# CW308T_EMF32GG11.net
KiCad netlist of a schematic drawn in Altium Designer
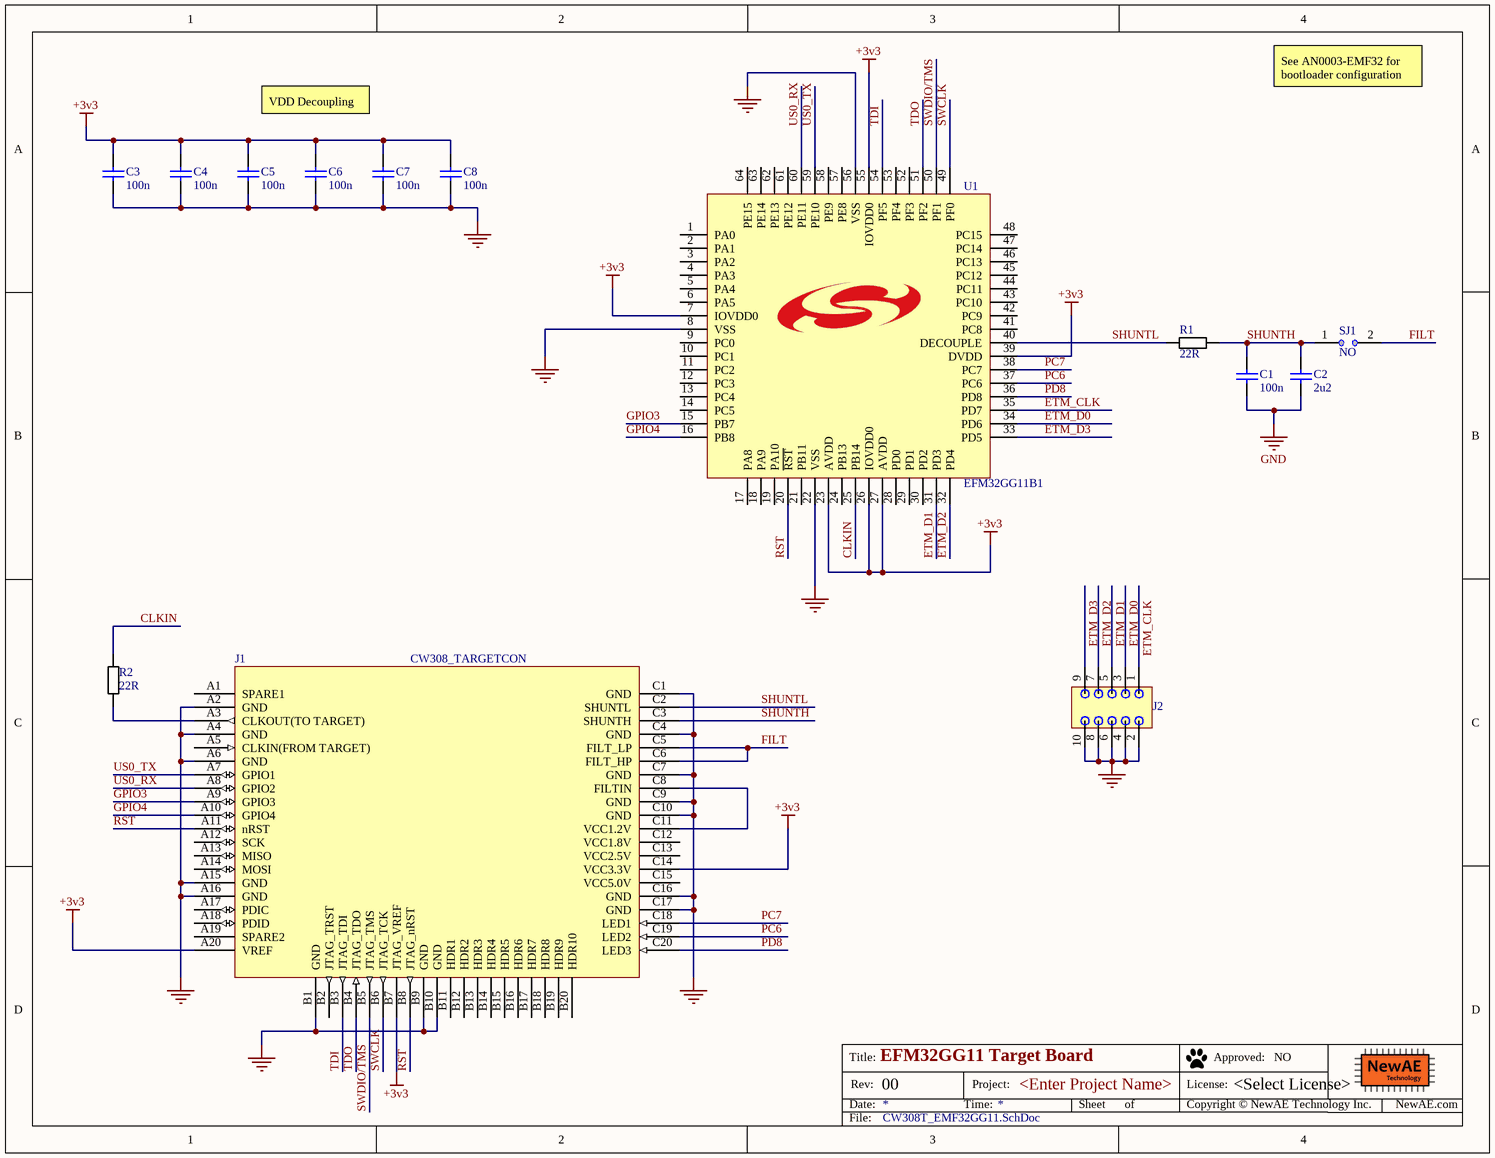
[diagram p0: CW308T_EMF32GG11.SchDoc]

(export (version "E")
  (design (tool "Eeschema 10.0.6"))
  (components
    (comp (ref "C1")
      (value "100n")
      (footprint "CAPC0603_M")
      (description "100n, 0603")
      (fields (field (name "PART NUMBER") "CCHIP-100n-0603"))
      (libsource (lib "NewAE_AltiumLib") (part "CAP"))
    )
    (comp (ref "C2")
      (value "2u2")
      (footprint "CAPC0603_M")
      (description "2u2, 0603")
      (fields (field (name "PART NUMBER") "CCHIP-2u2-0603"))
      (libsource (lib "NewAE_AltiumLib") (part "CAP"))
    )
    (comp (ref "C3")
      (value "100n")
      (footprint "CAPC0603_M")
      (description "100n, 0603")
      (fields (field (name "PART NUMBER") "CCHIP-100n-0603"))
      (libsource (lib "NewAE_AltiumLib") (part "CAP"))
    )
    (comp (ref "C4")
      (value "100n")
      (footprint "CAPC0603_M")
      (description "100n, 0603")
      (fields (field (name "PART NUMBER") "CCHIP-100n-0603"))
      (libsource (lib "NewAE_AltiumLib") (part "CAP"))
    )
    (comp (ref "C5")
      (value "100n")
      (footprint "CAPC0603_M")
      (description "100n, 0603")
      (fields (field (name "PART NUMBER") "CCHIP-100n-0603"))
      (libsource (lib "NewAE_AltiumLib") (part "CAP"))
    )
    (comp (ref "C6")
      (value "100n")
      (footprint "CAPC0603_M")
      (description "100n, 0603")
      (fields (field (name "PART NUMBER") "CCHIP-100n-0603"))
      (libsource (lib "NewAE_AltiumLib") (part "CAP"))
    )
    (comp (ref "C7")
      (value "100n")
      (footprint "CAPC0603_M")
      (description "100n, 0603")
      (fields (field (name "PART NUMBER") "CCHIP-100n-0603"))
      (libsource (lib "NewAE_AltiumLib") (part "CAP"))
    )
    (comp (ref "C8")
      (value "100n")
      (footprint "CAPC0603_M")
      (description "100n, 0603")
      (fields (field (name "PART NUMBER") "CCHIP-100n-0603"))
      (libsource (lib "NewAE_AltiumLib") (part "CAP"))
    )
    (comp (ref "J1")
      (value "CW308_TARGETCON")
      (footprint "CW308_TBOARD_CONN")
      (description "CW308 \"Standard\" Target Board Connector")
      (fields (field (name "PART NUMBER") "CW308_TBOARD"))
      (libsource (lib "NewAE_AltiumLib") (part "CW308_TBOARD"))
    )
    (comp (ref "J2")
      (value "1296-T10")
      (footprint "1296-T10")
      (description "Header, 10-pin, SMD, 0.05\"")
      (libsource (lib "NewAE_AltiumLib") (part "CON10_2ROW"))
    )
    (comp (ref "R1")
      (value "22R")
      (footprint "RESC1608X55N")
      (description "22R res, 0603, 1%, 1/10W")
      (fields (field (name "PART NUMBER") "RCHIP-22R-0603") (field (name "TOLERANCE") "1%"))
      (libsource (lib "NewAE_AltiumLib") (part "RES-EU"))
    )
    (comp (ref "R2")
      (value "22R")
      (footprint "RESC1608X55N")
      (description "22R res, 0603, 1%, 1/10W")
      (fields (field (name "PART NUMBER") "RCHIP-22R-0603") (field (name "TOLERANCE") "1%"))
      (libsource (lib "") (part "RES-EU_1"))
    )
    (comp (ref "SJ1")
      (value "NO")
      (footprint "SJ_2S_NO")
      (description "Solder Jumper, NO")
      (fields (field (name "PART NUMBER") "SJ_2S_NO"))
      (libsource (lib "NewAE_AltiumLib") (part "SJ_2S_NO"))
    )
    (comp (ref "U1")
      (value "EFM32GG11B1")
      (footprint "TQFP50P1200X1200X120-64N")
      (description "MCU Giant Gecko 11 Ultra Low Power MCU, Cortex-M4 72MHz QFP64 2048kB(Flash) 512kB(RAM) 53GPIO")
      (libsource (lib "NewAE_AltiumLib") (part "EFM32GG11B1"))
    )
  )
  (nets
    (net (code "1") (name "+3v3") (class "Default")
      (node (ref "C3") (pin "1") (pinfunction "1_1") (pintype "passive"))
      (node (ref "C4") (pin "1") (pinfunction "1_1") (pintype "passive"))
      (node (ref "C5") (pin "1") (pinfunction "1_1") (pintype "passive"))
      (node (ref "C6") (pin "1") (pinfunction "1_1") (pintype "passive"))
      (node (ref "C7") (pin "1") (pinfunction "1_1") (pintype "passive"))
      (node (ref "C8") (pin "1") (pinfunction "1_1") (pintype "passive"))
      (node (ref "J1") (pin "A20") (pinfunction "VREF_A20") (pintype "tri_state"))
      (node (ref "J1") (pin "B7") (pinfunction "JTAG_VREF_B7") (pintype "tri_state"))
      (node (ref "J1") (pin "C14") (pinfunction "VCC3.3V_C14") (pintype "power_in"))
      (node (ref "U1") (pin "23") (pinfunction "AVDD_23") (pintype "passive"))
      (node (ref "U1") (pin "26") (pinfunction "IOVDD0_26") (pintype "passive"))
      (node (ref "U1") (pin "27") (pinfunction "AVDD_27") (pintype "passive"))
      (node (ref "U1") (pin "39") (pinfunction "DVDD_39") (pintype "passive"))
      (node (ref "U1") (pin "55") (pinfunction "IOVDD0_55") (pintype "passive"))
      (node (ref "U1") (pin "7") (pinfunction "IOVDD0_7") (pintype "passive"))
    )
    (net (code "2") (name "/CLKIN") (class "Default")
      (node (ref "R2") (pin "1") (pinfunction "1_1") (pintype "passive"))
      (node (ref "U1") (pin "25") (pinfunction "PB14_25") (pintype "passive"))
    )
    (net (code "3") (name "/ETM_CLK") (class "Default")
      (node (ref "J2") (pin "1") (pinfunction "1_1") (pintype "passive"))
      (node (ref "U1") (pin "35") (pinfunction "PD7_35") (pintype "passive"))
    )
    (net (code "4") (name "/ETM_D0") (class "Default")
      (node (ref "J2") (pin "3") (pinfunction "3_3") (pintype "passive"))
      (node (ref "U1") (pin "34") (pinfunction "PD6_34") (pintype "passive"))
    )
    (net (code "5") (name "/ETM_D1") (class "Default")
      (node (ref "J2") (pin "5") (pinfunction "5_5") (pintype "passive"))
      (node (ref "U1") (pin "31") (pinfunction "PD3_31") (pintype "passive"))
    )
    (net (code "6") (name "/ETM_D2") (class "Default")
      (node (ref "J2") (pin "7") (pinfunction "7_7") (pintype "passive"))
      (node (ref "U1") (pin "32") (pinfunction "PD4_32") (pintype "passive"))
    )
    (net (code "7") (name "/ETM_D3") (class "Default")
      (node (ref "J2") (pin "9") (pinfunction "9_9") (pintype "passive"))
      (node (ref "U1") (pin "33") (pinfunction "PD5_33") (pintype "passive"))
    )
    (net (code "8") (name "/FILT") (class "Default")
      (node (ref "J1") (pin "C5") (pinfunction "FILT_LP_C5") (pintype "passive"))
      (node (ref "J1") (pin "C6") (pinfunction "FILT_HP_C6") (pintype "passive"))
      (node (ref "SJ1") (pin "2") (pinfunction "2_2") (pintype "passive"))
    )
    (net (code "9") (name "/GPIO3") (class "Default")
      (node (ref "J1") (pin "A9") (pinfunction "GPIO3_A9") (pintype "bidirectional"))
      (node (ref "U1") (pin "15") (pinfunction "PB7_15") (pintype "passive"))
    )
    (net (code "10") (name "/GPIO4") (class "Default")
      (node (ref "J1") (pin "A10") (pinfunction "GPIO4_A10") (pintype "bidirectional"))
      (node (ref "U1") (pin "16") (pinfunction "PB8_16") (pintype "passive"))
    )
    (net (code "11") (name "/PC6") (class "Default")
      (node (ref "J1") (pin "C19") (pinfunction "LED2_C19") (pintype "input"))
      (node (ref "U1") (pin "37") (pinfunction "PC6_37") (pintype "passive"))
    )
    (net (code "12") (name "/PC7") (class "Default")
      (node (ref "J1") (pin "C18") (pinfunction "LED1_C18") (pintype "input"))
      (node (ref "U1") (pin "38") (pinfunction "PC7_38") (pintype "passive"))
    )
    (net (code "13") (name "/PD8") (class "Default")
      (node (ref "J1") (pin "C20") (pinfunction "LED3_C20") (pintype "input"))
      (node (ref "U1") (pin "36") (pinfunction "PD8_36") (pintype "passive"))
    )
    (net (code "14") (name "/RST") (class "Default")
      (node (ref "J1") (pin "A11") (pinfunction "nRST_A11") (pintype "bidirectional"))
      (node (ref "J1") (pin "B8") (pinfunction "JTAG_nRST_B8") (pintype "output"))
      (node (ref "U1") (pin "20") (pinfunction "~{RST}_20") (pintype "passive"))
    )
    (net (code "15") (name "/SHUNTH") (class "Default")
      (node (ref "C1") (pin "1") (pinfunction "1_1") (pintype "passive"))
      (node (ref "C2") (pin "1") (pinfunction "1_1") (pintype "passive"))
      (node (ref "J1") (pin "C3") (pinfunction "SHUNTH_C3") (pintype "passive"))
      (node (ref "R1") (pin "2") (pinfunction "2_2") (pintype "passive"))
      (node (ref "SJ1") (pin "1") (pinfunction "1_1") (pintype "passive"))
    )
    (net (code "16") (name "/SHUNTL") (class "Default")
      (node (ref "J1") (pin "C2") (pinfunction "SHUNTL_C2") (pintype "passive"))
      (node (ref "R1") (pin "1") (pinfunction "1_1") (pintype "passive"))
      (node (ref "U1") (pin "40") (pinfunction "DECOUPLE_40") (pintype "passive"))
    )
    (net (code "17") (name "/SWCLK") (class "Default")
      (node (ref "J1") (pin "B6") (pinfunction "JTAG_TCK_B6") (pintype "output"))
      (node (ref "U1") (pin "49") (pinfunction "PF0_49") (pintype "passive"))
    )
    (net (code "18") (name "/SWDIO{slash}TMS") (class "Default")
      (node (ref "J1") (pin "B5") (pinfunction "JTAG_TMS_B5") (pintype "output"))
      (node (ref "U1") (pin "50") (pinfunction "PF1_50") (pintype "passive"))
    )
    (net (code "19") (name "/TDI") (class "Default")
      (node (ref "J1") (pin "B3") (pinfunction "JTAG_TDI_B3") (pintype "output"))
      (node (ref "U1") (pin "54") (pinfunction "PF5_54") (pintype "passive"))
    )
    (net (code "20") (name "/TDO") (class "Default")
      (node (ref "J1") (pin "B4") (pinfunction "JTAG_TDO_B4") (pintype "input"))
      (node (ref "U1") (pin "51") (pinfunction "PF2_51") (pintype "passive"))
    )
    (net (code "21") (name "/US0_RX") (class "Default")
      (node (ref "J1") (pin "A8") (pinfunction "GPIO2_A8") (pintype "bidirectional"))
      (node (ref "U1") (pin "60") (pinfunction "PE11_60") (pintype "passive"))
    )
    (net (code "22") (name "/US0_TX") (class "Default")
      (node (ref "J1") (pin "A7") (pinfunction "GPIO1_A7") (pintype "bidirectional"))
      (node (ref "U1") (pin "59") (pinfunction "PE10_59") (pintype "passive"))
    )
    (net (code "23") (name "GND") (class "Default")
      (node (ref "C1") (pin "2") (pinfunction "2_2") (pintype "passive"))
      (node (ref "C2") (pin "2") (pinfunction "2_2") (pintype "passive"))
      (node (ref "C3") (pin "2") (pinfunction "2_2") (pintype "passive"))
      (node (ref "C4") (pin "2") (pinfunction "2_2") (pintype "passive"))
      (node (ref "C5") (pin "2") (pinfunction "2_2") (pintype "passive"))
      (node (ref "C6") (pin "2") (pinfunction "2_2") (pintype "passive"))
      (node (ref "C7") (pin "2") (pinfunction "2_2") (pintype "passive"))
      (node (ref "C8") (pin "2") (pinfunction "2_2") (pintype "passive"))
      (node (ref "J1") (pin "A15") (pinfunction "GND_A15") (pintype "passive"))
      (node (ref "J1") (pin "A16") (pinfunction "GND_A16") (pintype "passive"))
      (node (ref "J1") (pin "A2") (pinfunction "GND_A2") (pintype "passive"))
      (node (ref "J1") (pin "A4") (pinfunction "GND_A4") (pintype "passive"))
      (node (ref "J1") (pin "A6") (pinfunction "GND_A6") (pintype "power_in"))
      (node (ref "J1") (pin "B1") (pinfunction "GND_B1") (pintype "passive"))
      (node (ref "J1") (pin "B10") (pinfunction "GND_B10") (pintype "passive"))
      (node (ref "J1") (pin "B9") (pinfunction "GND_B9") (pintype "passive"))
      (node (ref "J1") (pin "C1") (pinfunction "GND_C1") (pintype "power_in"))
      (node (ref "J1") (pin "C10") (pinfunction "GND_C10") (pintype "power_in"))
      (node (ref "J1") (pin "C16") (pinfunction "GND_C16") (pintype "power_in"))
      (node (ref "J1") (pin "C17") (pinfunction "GND_C17") (pintype "power_in"))
      (node (ref "J1") (pin "C4") (pinfunction "GND_C4") (pintype "power_in"))
      (node (ref "J1") (pin "C7") (pinfunction "GND_C7") (pintype "power_in"))
      (node (ref "J1") (pin "C9") (pinfunction "GND_C9") (pintype "power_in"))
      (node (ref "J2") (pin "10") (pinfunction "10_10") (pintype "passive"))
      (node (ref "J2") (pin "2") (pinfunction "2_2") (pintype "passive"))
      (node (ref "J2") (pin "4") (pinfunction "4_4") (pintype "passive"))
      (node (ref "J2") (pin "6") (pinfunction "6_6") (pintype "passive"))
      (node (ref "J2") (pin "8") (pinfunction "8_8") (pintype "passive"))
      (node (ref "U1") (pin "22") (pinfunction "VSS_22") (pintype "passive"))
      (node (ref "U1") (pin "56") (pinfunction "VSS_56") (pintype "passive"))
      (node (ref "U1") (pin "8") (pinfunction "VSS_8") (pintype "passive"))
    )
    (net (code "24") (name "Net-(J1-CLKOUT(TO_TARGET))") (class "Default")
      (node (ref "J1") (pin "A3") (pinfunction "CLKOUT(TO_TARGET)_A3") (pintype "output"))
      (node (ref "R2") (pin "2") (pinfunction "2_2") (pintype "passive"))
    )
    (net (code "25") (name "Net-(J1-FILTIN)") (class "Default")
      (node (ref "J1") (pin "C11") (pinfunction "VCC1.2V_C11") (pintype "power_in"))
      (node (ref "J1") (pin "C8") (pinfunction "FILTIN_C8") (pintype "passive"))
    )
    (net (code "26") (name "unconnected-(J1-CLKIN(FROM_TARGET)-PadA5)") (class "Default")
      (node (ref "J1") (pin "A5") (pinfunction "CLKIN(FROM_TARGET)_A5") (pintype "input"))
    )
    (net (code "27") (name "unconnected-(J1-HDR1-PadB11)") (class "Default")
      (node (ref "J1") (pin "B11") (pinfunction "HDR1_B11") (pintype "passive"))
    )
    (net (code "28") (name "unconnected-(J1-HDR2-PadB12)") (class "Default")
      (node (ref "J1") (pin "B12") (pinfunction "HDR2_B12") (pintype "passive"))
    )
    (net (code "29") (name "unconnected-(J1-HDR3-PadB13)") (class "Default")
      (node (ref "J1") (pin "B13") (pinfunction "HDR3_B13") (pintype "passive"))
    )
    (net (code "30") (name "unconnected-(J1-HDR4-PadB14)") (class "Default")
      (node (ref "J1") (pin "B14") (pinfunction "HDR4_B14") (pintype "passive"))
    )
    (net (code "31") (name "unconnected-(J1-HDR5-PadB15)") (class "Default")
      (node (ref "J1") (pin "B15") (pinfunction "HDR5_B15") (pintype "passive"))
    )
    (net (code "32") (name "unconnected-(J1-HDR6-PadB16)") (class "Default")
      (node (ref "J1") (pin "B16") (pinfunction "HDR6_B16") (pintype "passive"))
    )
    (net (code "33") (name "unconnected-(J1-HDR7-PadB17)") (class "Default")
      (node (ref "J1") (pin "B17") (pinfunction "HDR7_B17") (pintype "passive"))
    )
    (net (code "34") (name "unconnected-(J1-HDR8-PadB18)") (class "Default")
      (node (ref "J1") (pin "B18") (pinfunction "HDR8_B18") (pintype "passive"))
    )
    (net (code "35") (name "unconnected-(J1-HDR9-PadB19)") (class "Default")
      (node (ref "J1") (pin "B19") (pinfunction "HDR9_B19") (pintype "passive"))
    )
    (net (code "36") (name "unconnected-(J1-HDR10-PadB20)") (class "Default")
      (node (ref "J1") (pin "B20") (pinfunction "HDR10_B20") (pintype "passive"))
    )
    (net (code "37") (name "unconnected-(J1-JTAG_TRST-PadB2)") (class "Default")
      (node (ref "J1") (pin "B2") (pinfunction "JTAG_TRST_B2") (pintype "output"))
    )
    (net (code "38") (name "unconnected-(J1-MISO-PadA13)") (class "Default")
      (node (ref "J1") (pin "A13") (pinfunction "MISO_A13") (pintype "bidirectional"))
    )
    (net (code "39") (name "unconnected-(J1-MOSI-PadA14)") (class "Default")
      (node (ref "J1") (pin "A14") (pinfunction "MOSI_A14") (pintype "bidirectional"))
    )
    (net (code "40") (name "unconnected-(J1-PDIC-PadA17)") (class "Default")
      (node (ref "J1") (pin "A17") (pinfunction "PDIC_A17") (pintype "bidirectional"))
    )
    (net (code "41") (name "unconnected-(J1-PDID-PadA18)") (class "Default")
      (node (ref "J1") (pin "A18") (pinfunction "PDID_A18") (pintype "bidirectional"))
    )
    (net (code "42") (name "unconnected-(J1-SCK-PadA12)") (class "Default")
      (node (ref "J1") (pin "A12") (pinfunction "SCK_A12") (pintype "bidirectional"))
    )
    (net (code "43") (name "unconnected-(J1-SPARE1-PadA1)") (class "Default")
      (node (ref "J1") (pin "A1") (pinfunction "SPARE1_A1") (pintype "passive"))
    )
    (net (code "44") (name "unconnected-(J1-SPARE2-PadA19)") (class "Default")
      (node (ref "J1") (pin "A19") (pinfunction "SPARE2_A19") (pintype "passive"))
    )
    (net (code "45") (name "unconnected-(J1-VCC1.8V-PadC12)") (class "Default")
      (node (ref "J1") (pin "C12") (pinfunction "VCC1.8V_C12") (pintype "power_in"))
    )
    (net (code "46") (name "unconnected-(J1-VCC2.5V-PadC13)") (class "Default")
      (node (ref "J1") (pin "C13") (pinfunction "VCC2.5V_C13") (pintype "power_in"))
    )
    (net (code "47") (name "unconnected-(J1-VCC5.0V-PadC15)") (class "Default")
      (node (ref "J1") (pin "C15") (pinfunction "VCC5.0V_C15") (pintype "power_in"))
    )
    (net (code "48") (name "unconnected-(U1-PA0-Pad1)") (class "Default")
      (node (ref "U1") (pin "1") (pinfunction "PA0_1") (pintype "passive"))
    )
    (net (code "49") (name "unconnected-(U1-PA1-Pad2)") (class "Default")
      (node (ref "U1") (pin "2") (pinfunction "PA1_2") (pintype "passive"))
    )
    (net (code "50") (name "unconnected-(U1-PA2-Pad3)") (class "Default")
      (node (ref "U1") (pin "3") (pinfunction "PA2_3") (pintype "passive"))
    )
    (net (code "51") (name "unconnected-(U1-PA3-Pad4)") (class "Default")
      (node (ref "U1") (pin "4") (pinfunction "PA3_4") (pintype "passive"))
    )
    (net (code "52") (name "unconnected-(U1-PA4-Pad5)") (class "Default")
      (node (ref "U1") (pin "5") (pinfunction "PA4_5") (pintype "passive"))
    )
    (net (code "53") (name "unconnected-(U1-PA5-Pad6)") (class "Default")
      (node (ref "U1") (pin "6") (pinfunction "PA5_6") (pintype "passive"))
    )
    (net (code "54") (name "unconnected-(U1-PA8-Pad17)") (class "Default")
      (node (ref "U1") (pin "17") (pinfunction "PA8_17") (pintype "passive"))
    )
    (net (code "55") (name "unconnected-(U1-PA9-Pad18)") (class "Default")
      (node (ref "U1") (pin "18") (pinfunction "PA9_18") (pintype "passive"))
    )
    (net (code "56") (name "unconnected-(U1-PA10-Pad19)") (class "Default")
      (node (ref "U1") (pin "19") (pinfunction "PA10_19") (pintype "passive"))
    )
    (net (code "57") (name "unconnected-(U1-PB11-Pad21)") (class "Default")
      (node (ref "U1") (pin "21") (pinfunction "PB11_21") (pintype "passive"))
    )
    (net (code "58") (name "unconnected-(U1-PB13-Pad24)") (class "Default")
      (node (ref "U1") (pin "24") (pinfunction "PB13_24") (pintype "passive"))
    )
    (net (code "59") (name "unconnected-(U1-PC0-Pad9)") (class "Default")
      (node (ref "U1") (pin "9") (pinfunction "PC0_9") (pintype "passive"))
    )
    (net (code "60") (name "unconnected-(U1-PC1-Pad10)") (class "Default")
      (node (ref "U1") (pin "10") (pinfunction "PC1_10") (pintype "passive"))
    )
    (net (code "61") (name "unconnected-(U1-PC2-Pad11)") (class "Default")
      (node (ref "U1") (pin "11") (pinfunction "PC2_11") (pintype "passive"))
    )
    (net (code "62") (name "unconnected-(U1-PC3-Pad12)") (class "Default")
      (node (ref "U1") (pin "12") (pinfunction "PC3_12") (pintype "passive"))
    )
    (net (code "63") (name "unconnected-(U1-PC4-Pad13)") (class "Default")
      (node (ref "U1") (pin "13") (pinfunction "PC4_13") (pintype "passive"))
    )
    (net (code "64") (name "unconnected-(U1-PC5-Pad14)") (class "Default")
      (node (ref "U1") (pin "14") (pinfunction "PC5_14") (pintype "passive"))
    )
    (net (code "65") (name "unconnected-(U1-PC8-Pad41)") (class "Default")
      (node (ref "U1") (pin "41") (pinfunction "PC8_41") (pintype "passive"))
    )
    (net (code "66") (name "unconnected-(U1-PC9-Pad42)") (class "Default")
      (node (ref "U1") (pin "42") (pinfunction "PC9_42") (pintype "passive"))
    )
    (net (code "67") (name "unconnected-(U1-PC10-Pad43)") (class "Default")
      (node (ref "U1") (pin "43") (pinfunction "PC10_43") (pintype "passive"))
    )
    (net (code "68") (name "unconnected-(U1-PC11-Pad44)") (class "Default")
      (node (ref "U1") (pin "44") (pinfunction "PC11_44") (pintype "passive"))
    )
    (net (code "69") (name "unconnected-(U1-PC12-Pad45)") (class "Default")
      (node (ref "U1") (pin "45") (pinfunction "PC12_45") (pintype "passive"))
    )
    (net (code "70") (name "unconnected-(U1-PC13-Pad46)") (class "Default")
      (node (ref "U1") (pin "46") (pinfunction "PC13_46") (pintype "passive"))
    )
    (net (code "71") (name "unconnected-(U1-PC14-Pad47)") (class "Default")
      (node (ref "U1") (pin "47") (pinfunction "PC14_47") (pintype "passive"))
    )
    (net (code "72") (name "unconnected-(U1-PC15-Pad48)") (class "Default")
      (node (ref "U1") (pin "48") (pinfunction "PC15_48") (pintype "passive"))
    )
    (net (code "73") (name "unconnected-(U1-PD0-Pad28)") (class "Default")
      (node (ref "U1") (pin "28") (pinfunction "PD0_28") (pintype "passive"))
    )
    (net (code "74") (name "unconnected-(U1-PD1-Pad29)") (class "Default")
      (node (ref "U1") (pin "29") (pinfunction "PD1_29") (pintype "passive"))
    )
    (net (code "75") (name "unconnected-(U1-PD2-Pad30)") (class "Default")
      (node (ref "U1") (pin "30") (pinfunction "PD2_30") (pintype "passive"))
    )
    (net (code "76") (name "unconnected-(U1-PE8-Pad57)") (class "Default")
      (node (ref "U1") (pin "57") (pinfunction "PE8_57") (pintype "passive"))
    )
    (net (code "77") (name "unconnected-(U1-PE9-Pad58)") (class "Default")
      (node (ref "U1") (pin "58") (pinfunction "PE9_58") (pintype "passive"))
    )
    (net (code "78") (name "unconnected-(U1-PE12-Pad61)") (class "Default")
      (node (ref "U1") (pin "61") (pinfunction "PE12_61") (pintype "passive"))
    )
    (net (code "79") (name "unconnected-(U1-PE13-Pad62)") (class "Default")
      (node (ref "U1") (pin "62") (pinfunction "PE13_62") (pintype "passive"))
    )
    (net (code "80") (name "unconnected-(U1-PE14-Pad63)") (class "Default")
      (node (ref "U1") (pin "63") (pinfunction "PE14_63") (pintype "passive"))
    )
    (net (code "81") (name "unconnected-(U1-PE15-Pad64)") (class "Default")
      (node (ref "U1") (pin "64") (pinfunction "PE15_64") (pintype "passive"))
    )
    (net (code "82") (name "unconnected-(U1-PF3-Pad52)") (class "Default")
      (node (ref "U1") (pin "52") (pinfunction "PF3_52") (pintype "passive"))
    )
    (net (code "83") (name "unconnected-(U1-PF4-Pad53)") (class "Default")
      (node (ref "U1") (pin "53") (pinfunction "PF4_53") (pintype "passive"))
    )
  )
)
